# Adafruit_PCF8523_RTC.net
KiCad netlist of a schematic drawn in EAGLE
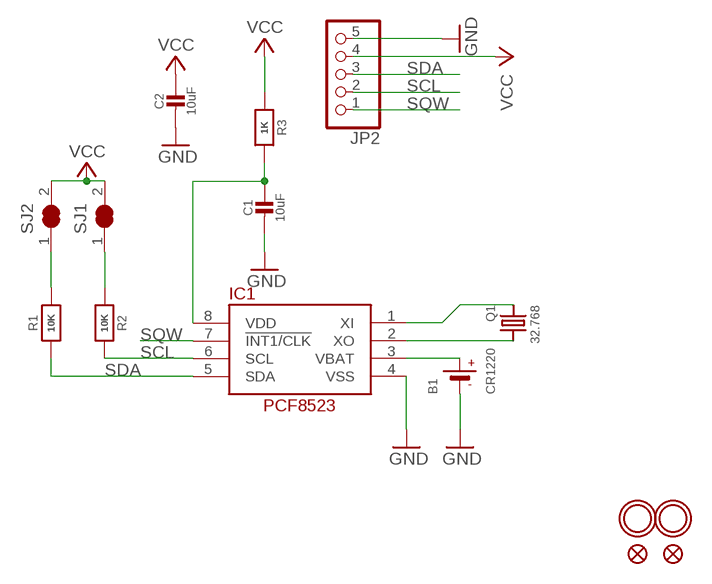
[diagram p0: schematic, sheet 1]

(export (version "E")
  (design (tool "Eeschema 10.0.6"))
  (components
    (comp (ref "B1")
      (value "CR1220")
      (footprint "eagle-import:CR1220")
      (libsource (lib "eagle-import") (part "BATTERYCR1220_SMT"))
    )
    (comp (ref "C1")
      (value "10uF")
      (footprint "eagle-import:0805-NO")
      (libsource (lib "eagle-import") (part "CAP_CERAMIC0805-NOOUTLINE"))
    )
    (comp (ref "C2")
      (value "10uF")
      (footprint "eagle-import:0805-NO")
      (libsource (lib "eagle-import") (part "CAP_CERAMIC0805-NOOUTLINE"))
    )
    (comp (ref "FID1")
      (value "FIDUCIAL\"\"")
      (footprint "eagle-import:FIDUCIAL_1MM")
      (libsource (lib "eagle-import") (part "FIDUCIAL{dblquote}{dblquote}"))
    )
    (comp (ref "FID2")
      (value "FIDUCIAL\"\"")
      (footprint "eagle-import:FIDUCIAL_1MM")
      (libsource (lib "eagle-import") (part "FIDUCIAL{dblquote}{dblquote}"))
    )
    (comp (ref "IC1")
      (value "RTC_PCF8523T")
      (footprint "eagle-import:SOIC8_150MIL")
      (libsource (lib "eagle-import") (part "RTC_PCF8523T"))
    )
    (comp (ref "JP2")
      (value "HEADER-1X576MIL")
      (footprint "eagle-import:1X05_ROUND_76")
      (libsource (lib "eagle-import") (part "HEADER-1X576MIL"))
    )
    (comp (ref "Q1")
      (value "32.768")
      (footprint "eagle-import:CRYSTAL_8X3.8")
      (libsource (lib "eagle-import") (part "CRYSTAL8.0X3.8"))
    )
    (comp (ref "R1")
      (value "10K")
      (footprint "eagle-import:0805-NO")
      (libsource (lib "eagle-import") (part "RESISTOR0805_NOOUTLINE"))
    )
    (comp (ref "R2")
      (value "10K")
      (footprint "eagle-import:0805-NO")
      (libsource (lib "eagle-import") (part "RESISTOR0805_NOOUTLINE"))
    )
    (comp (ref "R3")
      (value "1K")
      (footprint "eagle-import:0805-NO")
      (libsource (lib "eagle-import") (part "RESISTOR0805_NOOUTLINE"))
    )
    (comp (ref "SJ1")
      (value "SOLDERJUMPER_CLOSED")
      (footprint "eagle-import:SOLDERJUMPER_CLOSEDWIRE")
      (libsource (lib "eagle-import") (part "SOLDERJUMPER_CLOSED"))
    )
    (comp (ref "SJ2")
      (value "SOLDERJUMPER_CLOSED")
      (footprint "eagle-import:SOLDERJUMPER_CLOSEDWIRE")
      (libsource (lib "eagle-import") (part "SOLDERJUMPER_CLOSED"))
    )
    (comp (ref "U$1")
      (value "MOUNTINGHOLE2.0")
      (footprint "eagle-import:MOUNTINGHOLE_2.0_PLATED")
      (libsource (lib "eagle-import") (part "MOUNTINGHOLE2.0"))
    )
    (comp (ref "U$4")
      (value "MOUNTINGHOLE2.0")
      (footprint "eagle-import:MOUNTINGHOLE_2.0_PLATED")
      (libsource (lib "eagle-import") (part "MOUNTINGHOLE2.0"))
    )
  )
  (nets
    (net (code "1") (name "/SCL") (class "Default")
      (node (ref "IC1") (pin "6") (pinfunction "SCL_6") (pintype "bidirectional"))
      (node (ref "JP2") (pin "2") (pinfunction "2_2") (pintype "passive"))
      (node (ref "R2") (pin "2") (pinfunction "2_2") (pintype "passive"))
    )
    (net (code "2") (name "/SDA") (class "Default")
      (node (ref "IC1") (pin "5") (pinfunction "SDA_5") (pintype "bidirectional"))
      (node (ref "JP2") (pin "3") (pinfunction "3_3") (pintype "passive"))
      (node (ref "R1") (pin "1") (pinfunction "1_1") (pintype "passive"))
    )
    (net (code "3") (name "/SQW") (class "Default")
      (node (ref "IC1") (pin "7") (pinfunction "~{INT1/CLK}_7") (pintype "output"))
      (node (ref "JP2") (pin "1") (pinfunction "1_1") (pintype "passive"))
    )
    (net (code "4") (name "GND") (class "Default")
      (node (ref "B1") (pin "-") (pinfunction "-_-") (pintype "passive"))
      (node (ref "C1") (pin "2") (pinfunction "2_2") (pintype "passive"))
      (node (ref "C2") (pin "2") (pinfunction "2_2") (pintype "passive"))
      (node (ref "IC1") (pin "4") (pinfunction "VSS_4") (pintype "power_in"))
      (node (ref "JP2") (pin "5") (pinfunction "5_5") (pintype "passive"))
    )
    (net (code "5") (name "Net-(B1-+)") (class "Default")
      (node (ref "B1") (pin "+$1") (pinfunction "+_+$1") (pintype "passive"))
      (node (ref "IC1") (pin "3") (pinfunction "VBAT_3") (pintype "power_in"))
    )
    (net (code "6") (name "Net-(IC1-VDD)") (class "Default")
      (node (ref "C1") (pin "1") (pinfunction "1_1") (pintype "passive"))
      (node (ref "IC1") (pin "8") (pinfunction "VDD_8") (pintype "power_in"))
      (node (ref "R3") (pin "2") (pinfunction "2_2") (pintype "passive"))
    )
    (net (code "7") (name "Net-(IC1-XI)") (class "Default")
      (node (ref "IC1") (pin "1") (pinfunction "XI_1") (pintype "input"))
      (node (ref "Q1") (pin "P$1") (pinfunction "1_P$1") (pintype "passive"))
    )
    (net (code "8") (name "Net-(IC1-XO)") (class "Default")
      (node (ref "IC1") (pin "2") (pinfunction "XO_2") (pintype "output"))
      (node (ref "Q1") (pin "P$4") (pinfunction "2_P$4") (pintype "passive"))
    )
    (net (code "9") (name "Net-(R1-Pad2)") (class "Default")
      (node (ref "R1") (pin "2") (pinfunction "2_2") (pintype "passive"))
      (node (ref "SJ2") (pin "1") (pinfunction "1_1") (pintype "passive"))
    )
    (net (code "10") (name "Net-(R2-Pad1)") (class "Default")
      (node (ref "R2") (pin "1") (pinfunction "1_1") (pintype "passive"))
      (node (ref "SJ1") (pin "1") (pinfunction "1_1") (pintype "passive"))
    )
    (net (code "11") (name "VCC") (class "Default")
      (node (ref "C2") (pin "1") (pinfunction "1_1") (pintype "passive"))
      (node (ref "JP2") (pin "4") (pinfunction "4_4") (pintype "passive"))
      (node (ref "R3") (pin "1") (pinfunction "1_1") (pintype "passive"))
      (node (ref "SJ1") (pin "2") (pinfunction "2_2") (pintype "passive"))
      (node (ref "SJ2") (pin "2") (pinfunction "2_2") (pintype "passive"))
    )
  )
)
